# RH025_1.net
KiCad netlist of a schematic drawn in EAGLE
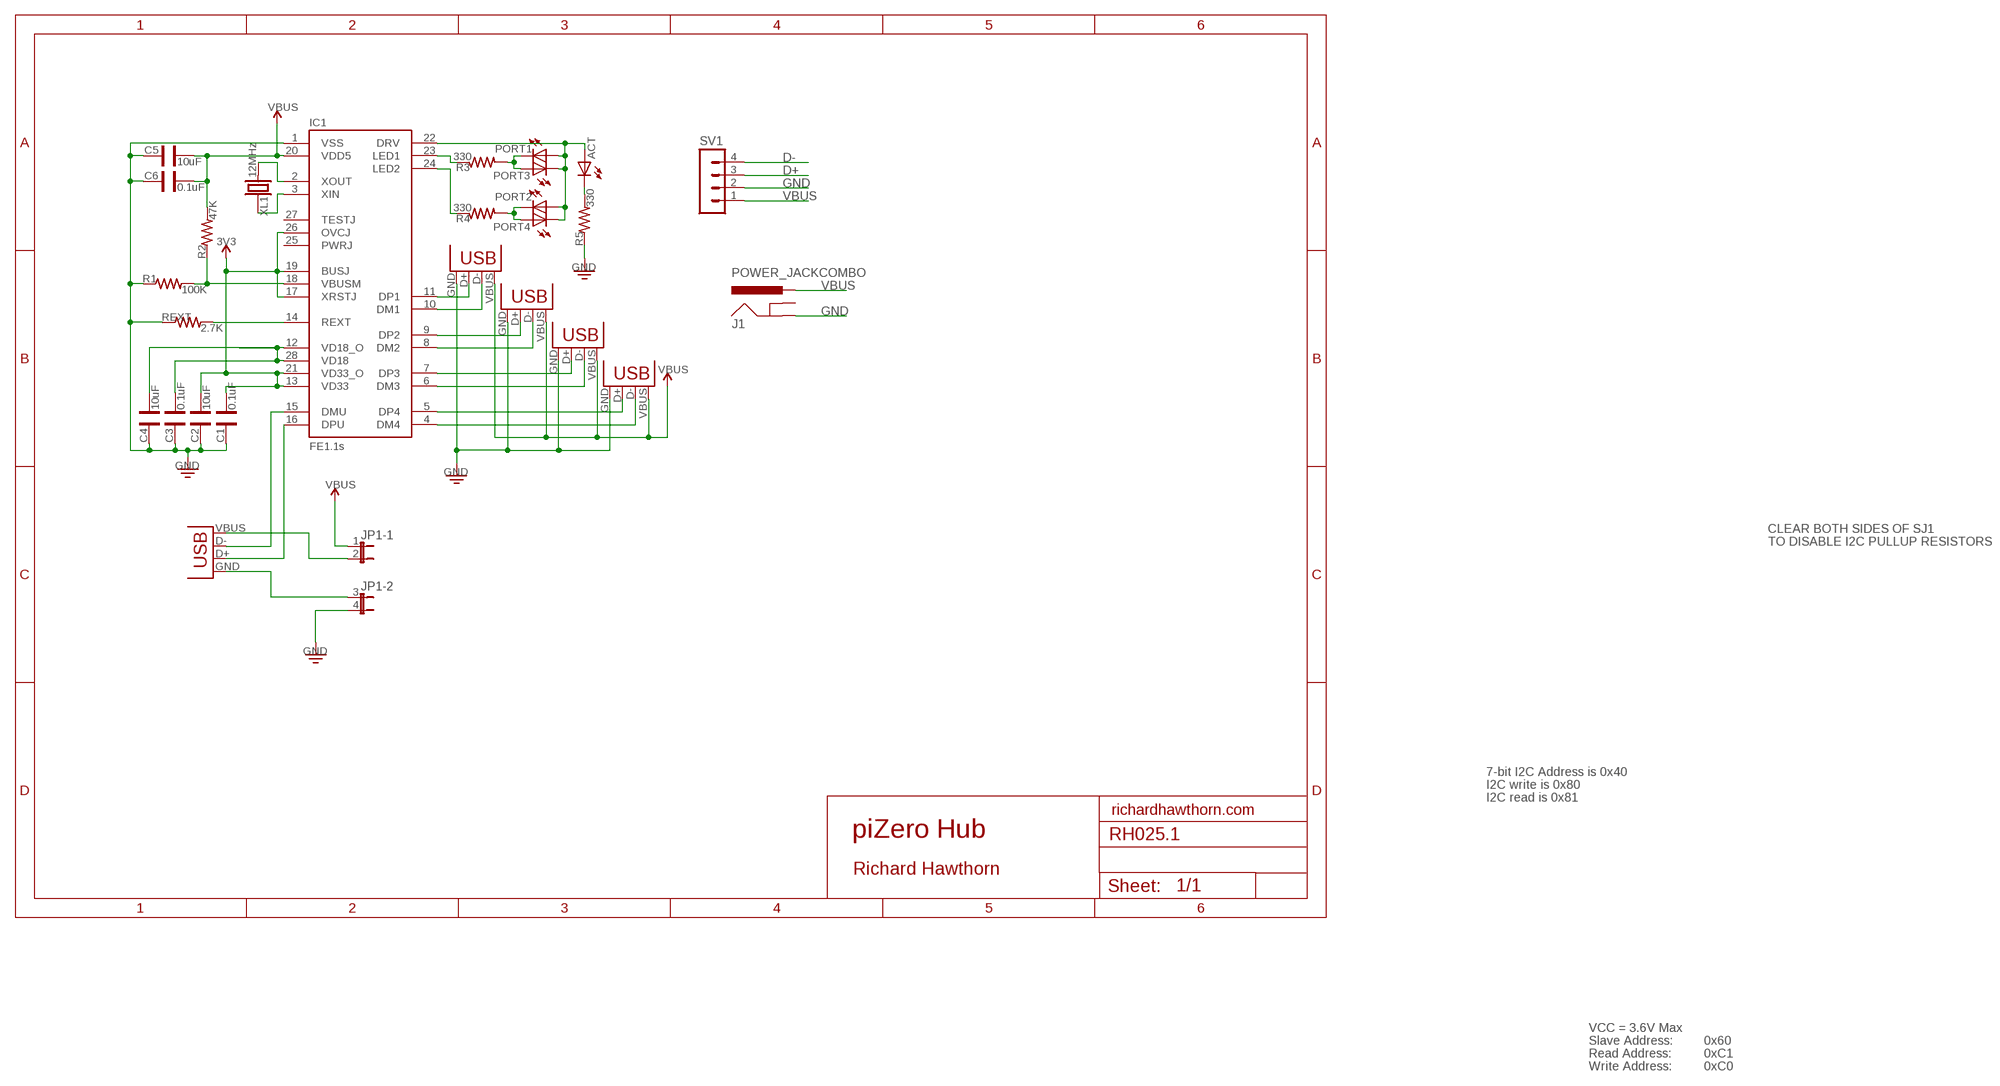
[diagram p0: schematic, sheet 1]

(export (version "E")
  (design (tool "Eeschema 10.0.6"))
  (components
    (comp (ref "ACT")
      (value "LED0603")
      (footprint "eagle-import:LED-0603")
      (libsource (lib "eagle-import") (part "LED0603"))
    )
    (comp (ref "C1")
      (value "0.1uF")
      (footprint "eagle-import:CAP-0603")
      (libsource (lib "eagle-import") (part "CAP0603"))
    )
    (comp (ref "C2")
      (value "10uF")
      (footprint "eagle-import:CAP-0603")
      (libsource (lib "eagle-import") (part "CAP0603"))
    )
    (comp (ref "C3")
      (value "0.1uF")
      (footprint "eagle-import:CAP-0603")
      (libsource (lib "eagle-import") (part "CAP0603"))
    )
    (comp (ref "C4")
      (value "10uF")
      (footprint "eagle-import:CAP-0603")
      (libsource (lib "eagle-import") (part "CAP0603"))
    )
    (comp (ref "C5")
      (value "10uF")
      (footprint "eagle-import:CAP-0603")
      (libsource (lib "eagle-import") (part "CAP0603"))
    )
    (comp (ref "C6")
      (value "0.1uF")
      (footprint "eagle-import:CAP-0603")
      (libsource (lib "eagle-import") (part "CAP0603"))
    )
    (comp (ref "IC1")
      (value "FE1.1S")
      (footprint "eagle-import:FE1.1S_SSOP-28")
      (libsource (lib "eagle-import") (part "FE1.1S"))
    )
    (comp (ref "J1")
      (value "POWER_JACKCOMBO")
      (footprint "eagle-import:POWER_JACK_COMBO")
      (libsource (lib "eagle-import") (part "POWER_JACKCOMBO"))
    )
    (comp (ref "JP1")
      (value "JP2QE")
      (footprint "eagle-import:JP2Q")
      (libsource (lib "eagle-import") (part "JP2QE"))
    )
    (comp (ref "PORT1")
      (value "LED0603")
      (footprint "eagle-import:LED-0603")
      (libsource (lib "eagle-import") (part "LED0603"))
    )
    (comp (ref "PORT2")
      (value "LED0603")
      (footprint "eagle-import:LED-0603")
      (libsource (lib "eagle-import") (part "LED0603"))
    )
    (comp (ref "PORT3")
      (value "LED0603")
      (footprint "eagle-import:LED-0603")
      (libsource (lib "eagle-import") (part "LED0603"))
    )
    (comp (ref "PORT4")
      (value "LED0603")
      (footprint "eagle-import:LED-0603")
      (libsource (lib "eagle-import") (part "LED0603"))
    )
    (comp (ref "R1")
      (value "100K")
      (footprint "eagle-import:RES-0603")
      (libsource (lib "eagle-import") (part "RES0603"))
    )
    (comp (ref "R2")
      (value "47K")
      (footprint "eagle-import:RES-0603")
      (libsource (lib "eagle-import") (part "RES0603"))
    )
    (comp (ref "R3")
      (value "330")
      (footprint "eagle-import:RES-0603")
      (libsource (lib "eagle-import") (part "RES0603"))
    )
    (comp (ref "R4")
      (value "330")
      (footprint "eagle-import:RES-0603")
      (libsource (lib "eagle-import") (part "RES0603"))
    )
    (comp (ref "R5")
      (value "330")
      (footprint "eagle-import:RES-0603")
      (libsource (lib "eagle-import") (part "RES0603"))
    )
    (comp (ref "REXT")
      (value "2.7K")
      (footprint "eagle-import:RES-0603")
      (libsource (lib "eagle-import") (part "RES0603"))
    )
    (comp (ref "SV1")
      (value "MA04-1")
      (footprint "eagle-import:MA04-1")
      (libsource (lib "eagle-import") (part "MA04-1"))
    )
    (comp (ref "USB1")
      (value "USBMICROB-PTH")
      (footprint "eagle-import:USB-MICROB-TH")
      (libsource (lib "eagle-import") (part "USBMICROB-PTH"))
    )
    (comp (ref "USB2")
      (value "USBA-PTH")
      (footprint "eagle-import:USB-A-F-PTH")
      (libsource (lib "eagle-import") (part "USBA-PTH"))
    )
    (comp (ref "USB3")
      (value "USBA-PTH")
      (footprint "eagle-import:USB-A-F-PTH")
      (libsource (lib "eagle-import") (part "USBA-PTH"))
    )
    (comp (ref "USB4")
      (value "USBA-PTH")
      (footprint "eagle-import:USB-A-F-PTH")
      (libsource (lib "eagle-import") (part "USBA-PTH"))
    )
    (comp (ref "USB5")
      (value "USBA-PTH")
      (footprint "eagle-import:USB-A-F-PTH")
      (libsource (lib "eagle-import") (part "USBA-PTH"))
    )
    (comp (ref "XL1")
      (value "12MHz")
      (footprint "eagle-import:HC49UP")
      (libsource (lib "eagle-import") (part "CRYSTALHC49UP"))
    )
  )
  (nets
    (net (code "1") (name "/D+") (class "Default")
      (node (ref "IC1") (pin "16") (pinfunction "DPU_16") (pintype "bidirectional"))
      (node (ref "SV1") (pin "3") (pinfunction "3_3") (pintype "passive"))
      (node (ref "USB1") (pin "D+") (pinfunction "D+_D+") (pintype "bidirectional"))
    )
    (net (code "2") (name "/D-") (class "Default")
      (node (ref "IC1") (pin "15") (pinfunction "DMU_15") (pintype "bidirectional"))
      (node (ref "SV1") (pin "4") (pinfunction "4_4") (pintype "passive"))
      (node (ref "USB1") (pin "D-") (pinfunction "D-_D-") (pintype "bidirectional"))
    )
    (net (code "3") (name "3V3") (class "Default")
      (node (ref "C1") (pin "1") (pinfunction "1_1") (pintype "passive"))
      (node (ref "C2") (pin "1") (pinfunction "1_1") (pintype "passive"))
      (node (ref "IC1") (pin "13") (pinfunction "VD33_13") (pintype "bidirectional"))
      (node (ref "IC1") (pin "17") (pinfunction "XRSTJ_17") (pintype "bidirectional"))
      (node (ref "IC1") (pin "19") (pinfunction "BUSJ_19") (pintype "bidirectional"))
      (node (ref "IC1") (pin "21") (pinfunction "VD33_O_21") (pintype "bidirectional"))
      (node (ref "IC1") (pin "26") (pinfunction "OVCJ_26") (pintype "bidirectional"))
    )
    (net (code "4") (name "GND") (class "Default")
      (node (ref "C1") (pin "2") (pinfunction "2_2") (pintype "passive"))
      (node (ref "C2") (pin "2") (pinfunction "2_2") (pintype "passive"))
      (node (ref "C3") (pin "2") (pinfunction "2_2") (pintype "passive"))
      (node (ref "C4") (pin "2") (pinfunction "2_2") (pintype "passive"))
      (node (ref "C5") (pin "2") (pinfunction "2_2") (pintype "passive"))
      (node (ref "C6") (pin "2") (pinfunction "2_2") (pintype "passive"))
      (node (ref "IC1") (pin "1") (pinfunction "VSS_1") (pintype "bidirectional"))
      (node (ref "J1") (pin "GND@1") (pinfunction "GND_GND@1") (pintype "bidirectional"))
      (node (ref "JP1") (pin "4") (pinfunction "2_4") (pintype "passive"))
      (node (ref "R1") (pin "1") (pinfunction "1_1") (pintype "passive"))
      (node (ref "R5") (pin "1") (pinfunction "1_1") (pintype "passive"))
      (node (ref "REXT") (pin "1") (pinfunction "1_1") (pintype "passive"))
      (node (ref "SV1") (pin "2") (pinfunction "2_2") (pintype "passive"))
      (node (ref "USB2") (pin "GND") (pinfunction "GND_GND") (pintype "bidirectional"))
      (node (ref "USB3") (pin "GND") (pinfunction "GND_GND") (pintype "bidirectional"))
      (node (ref "USB4") (pin "GND") (pinfunction "GND_GND") (pintype "bidirectional"))
      (node (ref "USB5") (pin "GND") (pinfunction "GND_GND") (pintype "bidirectional"))
    )
    (net (code "5") (name "Net-(ACT-PadC)") (class "Default")
      (node (ref "ACT") (pin "C") (pinfunction "C_C") (pintype "passive"))
      (node (ref "R5") (pin "2") (pinfunction "2_2") (pintype "passive"))
    )
    (net (code "6") (name "Net-(IC1-DM1)") (class "Default")
      (node (ref "IC1") (pin "10") (pinfunction "DM1_10") (pintype "bidirectional"))
      (node (ref "USB5") (pin "D-") (pinfunction "D-_D-") (pintype "bidirectional"))
    )
    (net (code "7") (name "Net-(IC1-DM2)") (class "Default")
      (node (ref "IC1") (pin "8") (pinfunction "DM2_8") (pintype "bidirectional"))
      (node (ref "USB4") (pin "D-") (pinfunction "D-_D-") (pintype "bidirectional"))
    )
    (net (code "8") (name "Net-(IC1-DM3)") (class "Default")
      (node (ref "IC1") (pin "6") (pinfunction "DM3_6") (pintype "bidirectional"))
      (node (ref "USB3") (pin "D-") (pinfunction "D-_D-") (pintype "bidirectional"))
    )
    (net (code "9") (name "Net-(IC1-DM4)") (class "Default")
      (node (ref "IC1") (pin "4") (pinfunction "DM4_4") (pintype "bidirectional"))
      (node (ref "USB2") (pin "D-") (pinfunction "D-_D-") (pintype "bidirectional"))
    )
    (net (code "10") (name "Net-(IC1-DP1)") (class "Default")
      (node (ref "IC1") (pin "11") (pinfunction "DP1_11") (pintype "bidirectional"))
      (node (ref "USB5") (pin "D+") (pinfunction "D+_D+") (pintype "bidirectional"))
    )
    (net (code "11") (name "Net-(IC1-DP2)") (class "Default")
      (node (ref "IC1") (pin "9") (pinfunction "DP2_9") (pintype "bidirectional"))
      (node (ref "USB4") (pin "D+") (pinfunction "D+_D+") (pintype "bidirectional"))
    )
    (net (code "12") (name "Net-(IC1-DP3)") (class "Default")
      (node (ref "IC1") (pin "7") (pinfunction "DP3_7") (pintype "bidirectional"))
      (node (ref "USB3") (pin "D+") (pinfunction "D+_D+") (pintype "bidirectional"))
    )
    (net (code "13") (name "Net-(IC1-DP4)") (class "Default")
      (node (ref "IC1") (pin "5") (pinfunction "DP4_5") (pintype "bidirectional"))
      (node (ref "USB2") (pin "D+") (pinfunction "D+_D+") (pintype "bidirectional"))
    )
    (net (code "14") (name "Net-(IC1-DRV)") (class "Default")
      (node (ref "ACT") (pin "A") (pinfunction "A_A") (pintype "passive"))
      (node (ref "IC1") (pin "22") (pinfunction "DRV_22") (pintype "bidirectional"))
      (node (ref "PORT1") (pin "A") (pinfunction "A_A") (pintype "passive"))
      (node (ref "PORT2") (pin "A") (pinfunction "A_A") (pintype "passive"))
      (node (ref "PORT3") (pin "C") (pinfunction "C_C") (pintype "passive"))
      (node (ref "PORT4") (pin "C") (pinfunction "C_C") (pintype "passive"))
    )
    (net (code "15") (name "Net-(IC1-LED1)") (class "Default")
      (node (ref "IC1") (pin "23") (pinfunction "LED1_23") (pintype "bidirectional"))
      (node (ref "R3") (pin "1") (pinfunction "1_1") (pintype "passive"))
    )
    (net (code "16") (name "Net-(IC1-LED2)") (class "Default")
      (node (ref "IC1") (pin "24") (pinfunction "LED2_24") (pintype "bidirectional"))
      (node (ref "R4") (pin "1") (pinfunction "1_1") (pintype "passive"))
    )
    (net (code "17") (name "Net-(IC1-REXT)") (class "Default")
      (node (ref "IC1") (pin "14") (pinfunction "REXT_14") (pintype "bidirectional"))
      (node (ref "REXT") (pin "2") (pinfunction "2_2") (pintype "passive"))
    )
    (net (code "18") (name "Net-(IC1-VBUSM)") (class "Default")
      (node (ref "IC1") (pin "18") (pinfunction "VBUSM_18") (pintype "bidirectional"))
      (node (ref "R1") (pin "2") (pinfunction "2_2") (pintype "passive"))
      (node (ref "R2") (pin "1") (pinfunction "1_1") (pintype "passive"))
    )
    (net (code "19") (name "Net-(IC1-VD18)") (class "Default")
      (node (ref "C3") (pin "1") (pinfunction "1_1") (pintype "passive"))
      (node (ref "C4") (pin "1") (pinfunction "1_1") (pintype "passive"))
      (node (ref "IC1") (pin "12") (pinfunction "VD18_O_12") (pintype "bidirectional"))
      (node (ref "IC1") (pin "28") (pinfunction "VD18_28") (pintype "bidirectional"))
    )
    (net (code "20") (name "Net-(IC1-XIN)") (class "Default")
      (node (ref "IC1") (pin "3") (pinfunction "XIN_3") (pintype "bidirectional"))
      (node (ref "XL1") (pin "1") (pinfunction "1_1") (pintype "passive"))
    )
    (net (code "21") (name "Net-(IC1-XOUT)") (class "Default")
      (node (ref "IC1") (pin "2") (pinfunction "XOUT_2") (pintype "bidirectional"))
      (node (ref "XL1") (pin "2") (pinfunction "2_2") (pintype "passive"))
    )
    (net (code "22") (name "Net-(JP1-Pad2)") (class "Default")
      (node (ref "JP1") (pin "2") (pinfunction "2_2") (pintype "passive"))
      (node (ref "USB1") (pin "VBUS") (pinfunction "VBUS_VBUS") (pintype "bidirectional"))
    )
    (net (code "23") (name "Net-(JP1B-1)") (class "Default")
      (node (ref "JP1") (pin "3") (pinfunction "1_3") (pintype "passive"))
      (node (ref "USB1") (pin "GND") (pinfunction "GND_GND") (pintype "bidirectional"))
    )
    (net (code "24") (name "Net-(PORT1-PadC)") (class "Default")
      (node (ref "PORT1") (pin "C") (pinfunction "C_C") (pintype "passive"))
      (node (ref "PORT3") (pin "A") (pinfunction "A_A") (pintype "passive"))
      (node (ref "R3") (pin "2") (pinfunction "2_2") (pintype "passive"))
    )
    (net (code "25") (name "Net-(PORT2-PadC)") (class "Default")
      (node (ref "PORT2") (pin "C") (pinfunction "C_C") (pintype "passive"))
      (node (ref "PORT4") (pin "A") (pinfunction "A_A") (pintype "passive"))
      (node (ref "R4") (pin "2") (pinfunction "2_2") (pintype "passive"))
    )
    (net (code "26") (name "VBUS") (class "Default")
      (node (ref "C5") (pin "1") (pinfunction "1_1") (pintype "passive"))
      (node (ref "C6") (pin "1") (pinfunction "1_1") (pintype "passive"))
      (node (ref "IC1") (pin "20") (pinfunction "VDD5_20") (pintype "bidirectional"))
      (node (ref "J1") (pin "POWER") (pinfunction "PWR_POWER") (pintype "bidirectional"))
      (node (ref "JP1") (pin "1") (pinfunction "1_1") (pintype "passive"))
      (node (ref "R2") (pin "2") (pinfunction "2_2") (pintype "passive"))
      (node (ref "SV1") (pin "1") (pinfunction "1_1") (pintype "passive"))
      (node (ref "USB2") (pin "VBUS") (pinfunction "VBUS_VBUS") (pintype "bidirectional"))
      (node (ref "USB3") (pin "VBUS") (pinfunction "VBUS_VBUS") (pintype "bidirectional"))
      (node (ref "USB4") (pin "VBUS") (pinfunction "VBUS_VBUS") (pintype "bidirectional"))
      (node (ref "USB5") (pin "VBUS") (pinfunction "VBUS_VBUS") (pintype "bidirectional"))
    )
    (net (code "27") (name "unconnected-(IC1-PWRJ-Pad25)") (class "Default")
      (node (ref "IC1") (pin "25") (pinfunction "PWRJ_25") (pintype "bidirectional"))
    )
    (net (code "28") (name "unconnected-(IC1-TESTJ-Pad27)") (class "Default")
      (node (ref "IC1") (pin "27") (pinfunction "TESTJ_27") (pintype "bidirectional"))
    )
    (net (code "29") (name "unconnected-(J1-GNDBREAK-PadGND)") (class "Default")
      (node (ref "J1") (pin "GND") (pinfunction "GNDBREAK_GND") (pintype "bidirectional"))
    )
  )
)
